# Motor_and_Gas.net
KiCad netlist of a schematic drawn in EAGLE
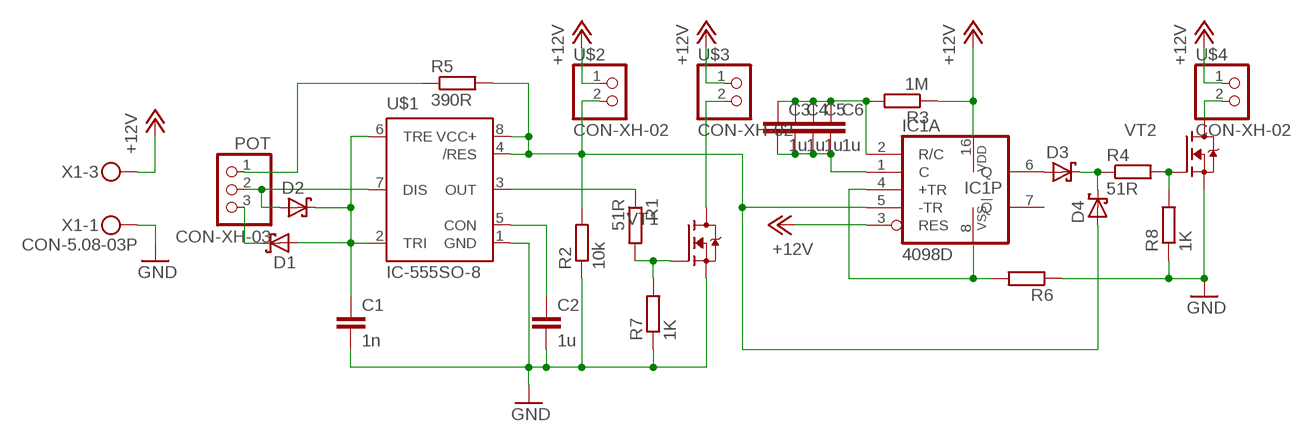
[diagram p0: schematic, sheet 1]

(export (version "E")
  (design (tool "Eeschema 10.0.6"))
  (components
    (comp (ref "C1")
      (value "1n")
      (footprint "eagle-import:C1206")
      (libsource (lib "eagle-import") (part "CAP_1206"))
    )
    (comp (ref "C2")
      (value "1u")
      (footprint "eagle-import:C1206")
      (libsource (lib "eagle-import") (part "CAP_1206"))
    )
    (comp (ref "C3")
      (value "1u")
      (footprint "eagle-import:C1206")
      (libsource (lib "eagle-import") (part "CAP_1206"))
    )
    (comp (ref "C4")
      (value "1u")
      (footprint "eagle-import:C1206")
      (libsource (lib "eagle-import") (part "CAP_1206"))
    )
    (comp (ref "C5")
      (value "1u")
      (footprint "eagle-import:C1206")
      (libsource (lib "eagle-import") (part "CAP_1206"))
    )
    (comp (ref "C6")
      (value "1u")
      (footprint "eagle-import:C1206")
      (libsource (lib "eagle-import") (part "CAP_1206"))
    )
    (comp (ref "D1")
      (value "DIODE-SH_SOD523")
      (footprint "eagle-import:SOD523")
      (libsource (lib "eagle-import") (part "DIODE-SH_SOD523"))
    )
    (comp (ref "D2")
      (value "DIODE-SH_SOD523")
      (footprint "eagle-import:SOD523")
      (libsource (lib "eagle-import") (part "DIODE-SH_SOD523"))
    )
    (comp (ref "D3")
      (value "DIODE-SH_SOD523")
      (footprint "eagle-import:SOD523")
      (libsource (lib "eagle-import") (part "DIODE-SH_SOD523"))
    )
    (comp (ref "D4")
      (value "DIODE-SH_SOD523")
      (footprint "eagle-import:SOD523")
      (libsource (lib "eagle-import") (part "DIODE-SH_SOD523"))
    )
    (comp (ref "IC1")
      (value "4098D")
      (footprint "eagle-import:SO16")
      (libsource (lib "eagle-import") (part "4098D"))
    )
    (comp (ref "POT")
      (value "CON-XH-03")
      (footprint "eagle-import:XH-03")
      (libsource (lib "eagle-import") (part "CON-XH-03"))
    )
    (comp (ref "R1")
      (value "51R")
      (footprint "eagle-import:R1206")
      (libsource (lib "eagle-import") (part "R_1206"))
    )
    (comp (ref "R2")
      (value "10k")
      (footprint "eagle-import:R1206")
      (libsource (lib "eagle-import") (part "R_1206"))
    )
    (comp (ref "R3")
      (value "1M")
      (footprint "eagle-import:R1206")
      (libsource (lib "eagle-import") (part "R_1206"))
    )
    (comp (ref "R4")
      (value "51R")
      (footprint "eagle-import:R1206")
      (libsource (lib "eagle-import") (part "R_1206"))
    )
    (comp (ref "R5")
      (value "390R")
      (footprint "eagle-import:R1206")
      (libsource (lib "eagle-import") (part "R_1206"))
    )
    (comp (ref "R6")
      (value "R_0805")
      (footprint "eagle-import:R0805")
      (libsource (lib "eagle-import") (part "R_0805"))
    )
    (comp (ref "R7")
      (value "1K")
      (footprint "eagle-import:R0805")
      (libsource (lib "eagle-import") (part "R_0805"))
    )
    (comp (ref "R8")
      (value "1K")
      (footprint "eagle-import:R0805")
      (libsource (lib "eagle-import") (part "R_0805"))
    )
    (comp (ref "U$1")
      (value "IC-555SO-8")
      (footprint "eagle-import:SOIC127P600X175-8")
      (libsource (lib "eagle-import") (part "IC-555SO-8"))
    )
    (comp (ref "U$2")
      (value "CON-XH-02")
      (footprint "eagle-import:XH-02")
      (libsource (lib "eagle-import") (part "CON-XH-02"))
    )
    (comp (ref "U$3")
      (value "CON-XH-02")
      (footprint "eagle-import:XH-02")
      (libsource (lib "eagle-import") (part "CON-XH-02"))
    )
    (comp (ref "U$4")
      (value "CON-XH-02")
      (footprint "eagle-import:XH-02")
      (libsource (lib "eagle-import") (part "CON-XH-02"))
    )
    (comp (ref "VT1")
      (value "FET-NPF-6X5")
      (footprint "eagle-import:POWERFLAT-5X6")
      (libsource (lib "eagle-import") (part "FET-NPF-6X5"))
    )
    (comp (ref "VT2")
      (value "FET-NPF-6X5")
      (footprint "eagle-import:POWERFLAT-5X6")
      (libsource (lib "eagle-import") (part "FET-NPF-6X5"))
    )
    (comp (ref "X1")
      (value "CON-5.08-03P")
      (footprint "eagle-import:MKDSN1,5_3-5,08")
      (libsource (lib "eagle-import") (part "CON-5.08-03P"))
    )
  )
  (nets
    (net (code "1") (name "+12V") (class "Default")
      (node (ref "IC1") (pin "16") (pinfunction "VDD_16") (pintype "power_in"))
      (node (ref "IC1") (pin "3") (pinfunction "RES_3") (pintype "input"))
      (node (ref "R3") (pin "1") (pinfunction "1_1") (pintype "passive"))
      (node (ref "U$2") (pin "1") (pinfunction "1_1") (pintype "passive"))
      (node (ref "U$3") (pin "1") (pinfunction "1_1") (pintype "passive"))
      (node (ref "U$4") (pin "1") (pinfunction "1_1") (pintype "passive"))
      (node (ref "X1") (pin "3") (pinfunction "KL_3") (pintype "passive"))
    )
    (net (code "2") (name "GND") (class "Default")
      (node (ref "C1") (pin "2") (pinfunction "2_2") (pintype "passive"))
      (node (ref "C2") (pin "2") (pinfunction "2_2") (pintype "passive"))
      (node (ref "R2") (pin "1") (pinfunction "1_1") (pintype "passive"))
      (node (ref "R6") (pin "1") (pinfunction "1_1") (pintype "passive"))
      (node (ref "R7") (pin "1") (pinfunction "1_1") (pintype "passive"))
      (node (ref "R8") (pin "1") (pinfunction "1_1") (pintype "passive"))
      (node (ref "U$1") (pin "1") (pinfunction "GND_1") (pintype "power_in"))
      (node (ref "VT1") (pin "S1") (pinfunction "S_S1") (pintype "passive"))
      (node (ref "VT1") (pin "S2") (pinfunction "S_S2") (pintype "passive"))
      (node (ref "VT1") (pin "S3") (pinfunction "S_S3") (pintype "passive"))
      (node (ref "VT2") (pin "S1") (pinfunction "S_S1") (pintype "passive"))
      (node (ref "VT2") (pin "S2") (pinfunction "S_S2") (pintype "passive"))
      (node (ref "VT2") (pin "S3") (pinfunction "S_S3") (pintype "passive"))
      (node (ref "X1") (pin "1") (pinfunction "KL_1") (pintype "passive"))
    )
    (net (code "3") (name "Net-(D1-PadC)") (class "Default")
      (node (ref "D1") (pin "C") (pinfunction "C_C") (pintype "passive"))
      (node (ref "POT") (pin "3") (pinfunction "3_3") (pintype "passive"))
    )
    (net (code "4") (name "Net-(D3-PadC)") (class "Default")
      (node (ref "D3") (pin "C") (pinfunction "C_C") (pintype "passive"))
      (node (ref "D4") (pin "C") (pinfunction "C_C") (pintype "passive"))
      (node (ref "R4") (pin "1") (pinfunction "1_1") (pintype "passive"))
    )
    (net (code "5") (name "Net-(IC1A-+TR)") (class "Default")
      (node (ref "IC1") (pin "4") (pinfunction "+TR_4") (pintype "input"))
      (node (ref "IC1") (pin "8") (pinfunction "VSS_8") (pintype "power_in"))
      (node (ref "R6") (pin "2") (pinfunction "2_2") (pintype "passive"))
    )
    (net (code "6") (name "Net-(IC1A--TR)") (class "Default")
      (node (ref "D4") (pin "A") (pinfunction "A_A") (pintype "passive"))
      (node (ref "IC1") (pin "5") (pinfunction "-TR_5") (pintype "input"))
      (node (ref "R2") (pin "2") (pinfunction "2_2") (pintype "passive"))
      (node (ref "R5") (pin "2") (pinfunction "2_2") (pintype "passive"))
      (node (ref "U$1") (pin "4") (pinfunction "/RES_4") (pintype "input"))
      (node (ref "U$1") (pin "8") (pinfunction "VCC+_8") (pintype "power_in"))
      (node (ref "U$2") (pin "2") (pinfunction "2_2") (pintype "passive"))
    )
    (net (code "7") (name "Net-(IC1A-C)") (class "Default")
      (node (ref "C3") (pin "2") (pinfunction "2_2") (pintype "passive"))
      (node (ref "C4") (pin "2") (pinfunction "2_2") (pintype "passive"))
      (node (ref "C5") (pin "2") (pinfunction "2_2") (pintype "passive"))
      (node (ref "C6") (pin "2") (pinfunction "2_2") (pintype "passive"))
      (node (ref "IC1") (pin "1") (pinfunction "C_1") (pintype "input"))
    )
    (net (code "8") (name "Net-(IC1A-Q)") (class "Default")
      (node (ref "D3") (pin "A") (pinfunction "A_A") (pintype "passive"))
      (node (ref "IC1") (pin "6") (pinfunction "Q_6") (pintype "output"))
    )
    (net (code "9") (name "Net-(IC1A-R{slash}C)") (class "Default")
      (node (ref "C3") (pin "1") (pinfunction "1_1") (pintype "passive"))
      (node (ref "C4") (pin "1") (pinfunction "1_1") (pintype "passive"))
      (node (ref "C5") (pin "1") (pinfunction "1_1") (pintype "passive"))
      (node (ref "C6") (pin "1") (pinfunction "1_1") (pintype "passive"))
      (node (ref "IC1") (pin "2") (pinfunction "R/C_2") (pintype "input"))
      (node (ref "R3") (pin "2") (pinfunction "2_2") (pintype "passive"))
    )
    (net (code "10") (name "Net-(POT-Pad1)") (class "Default")
      (node (ref "POT") (pin "1") (pinfunction "1_1") (pintype "passive"))
      (node (ref "R5") (pin "1") (pinfunction "1_1") (pintype "passive"))
    )
    (net (code "11") (name "Net-(R1-Pad2)") (class "Default")
      (node (ref "R1") (pin "2") (pinfunction "2_2") (pintype "passive"))
      (node (ref "R7") (pin "2") (pinfunction "2_2") (pintype "passive"))
      (node (ref "VT1") (pin "G") (pinfunction "G_G") (pintype "passive"))
    )
    (net (code "12") (name "Net-(R4-Pad2)") (class "Default")
      (node (ref "R4") (pin "2") (pinfunction "2_2") (pintype "passive"))
      (node (ref "R8") (pin "2") (pinfunction "2_2") (pintype "passive"))
      (node (ref "VT2") (pin "G") (pinfunction "G_G") (pintype "passive"))
    )
    (net (code "13") (name "Net-(U$1-CON)") (class "Default")
      (node (ref "C2") (pin "1") (pinfunction "1_1") (pintype "passive"))
      (node (ref "U$1") (pin "5") (pinfunction "CON_5") (pintype "input"))
    )
    (net (code "14") (name "Net-(U$1-DIS)") (class "Default")
      (node (ref "D2") (pin "A") (pinfunction "A_A") (pintype "passive"))
      (node (ref "POT") (pin "2") (pinfunction "2_2") (pintype "passive"))
      (node (ref "U$1") (pin "7") (pinfunction "DIS_7") (pintype "input"))
    )
    (net (code "15") (name "Net-(U$1-OUT)") (class "Default")
      (node (ref "R1") (pin "1") (pinfunction "1_1") (pintype "passive"))
      (node (ref "U$1") (pin "3") (pinfunction "OUT_3") (pintype "output"))
    )
    (net (code "16") (name "Net-(U$1-TRE)") (class "Default")
      (node (ref "C1") (pin "1") (pinfunction "1_1") (pintype "passive"))
      (node (ref "D1") (pin "A") (pinfunction "A_A") (pintype "passive"))
      (node (ref "D2") (pin "C") (pinfunction "C_C") (pintype "passive"))
      (node (ref "U$1") (pin "2") (pinfunction "TRI_2") (pintype "input"))
      (node (ref "U$1") (pin "6") (pinfunction "TRE_6") (pintype "input"))
    )
    (net (code "17") (name "Net-(VT1-D)") (class "Default")
      (node (ref "U$3") (pin "2") (pinfunction "2_2") (pintype "passive"))
      (node (ref "VT1") (pin "D1") (pinfunction "D_D1") (pintype "passive"))
    )
    (net (code "18") (name "Net-(VT2-D)") (class "Default")
      (node (ref "U$4") (pin "2") (pinfunction "2_2") (pintype "passive"))
      (node (ref "VT2") (pin "D1") (pinfunction "D_D1") (pintype "passive"))
    )
    (net (code "19") (name "unconnected-(IC1A-~{Q}-Pad7)") (class "Default")
      (node (ref "IC1") (pin "7") (pinfunction "~{Q}_7") (pintype "output"))
    )
  )
)
